# midimixer-st-eval.net
KiCad netlist of a schematic drawn in EAGLE
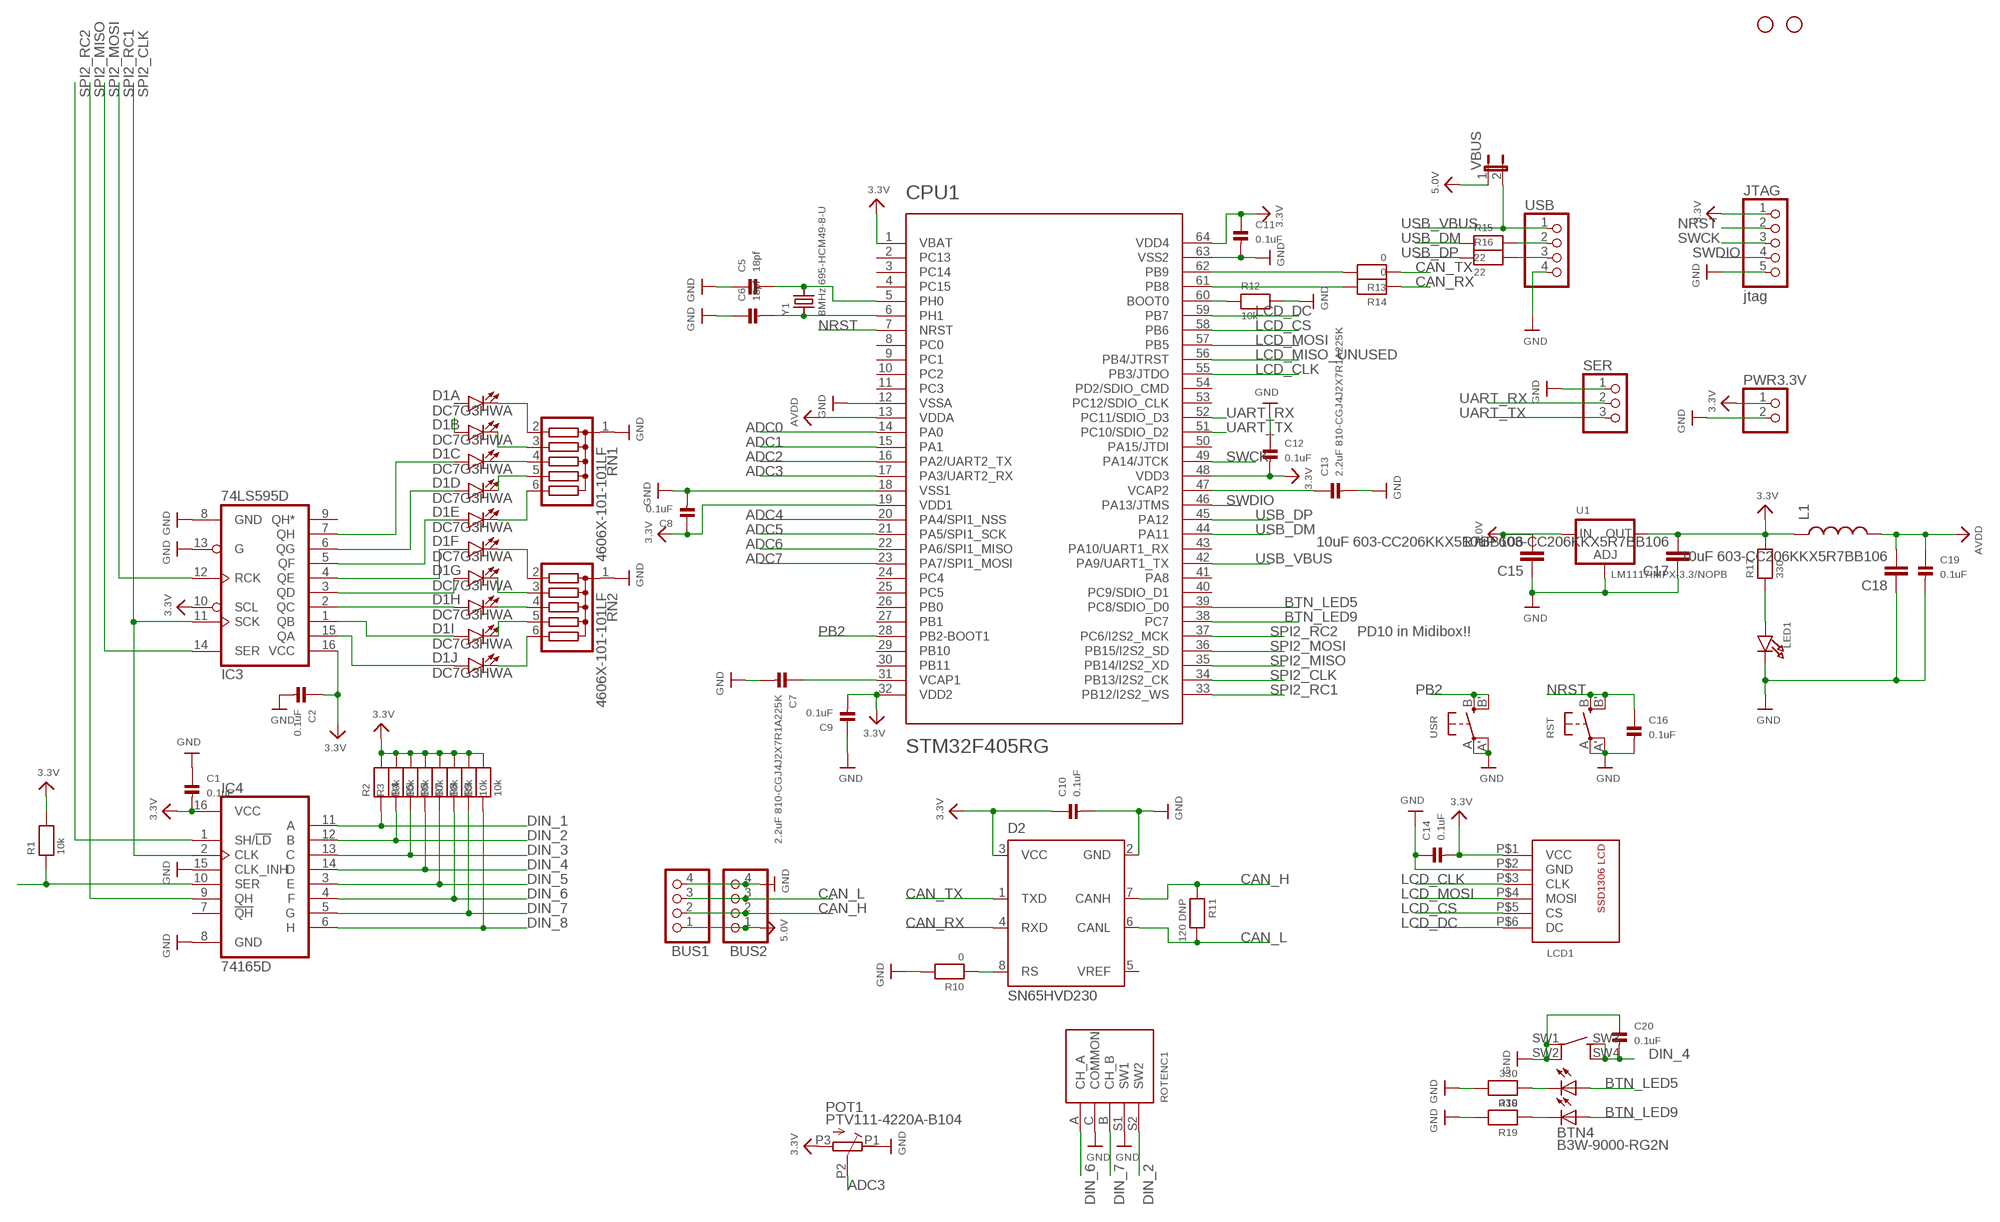
[diagram p0: schematic, sheet 1]

(export (version "E")
  (design (tool "Eeschema 10.0.6"))
  (components
    (comp (ref "BTN4")
      (value "B3W-9000-RG2N")
      (footprint "eagle-import:B3W-9000-X2X")
      (libsource (lib "eagle-import") (part "B3W-9000-RG2N"))
    )
    (comp (ref "BUS1")
      (value "HEADER-1X4ROUND")
      (footprint "eagle-import:1X04_ROUND")
      (libsource (lib "eagle-import") (part "HEADER-1X4ROUND"))
    )
    (comp (ref "BUS2")
      (value "HEADER-1X4ROUND")
      (footprint "eagle-import:1X04_ROUND")
      (libsource (lib "eagle-import") (part "HEADER-1X4ROUND"))
    )
    (comp (ref "C1")
      (value "0.1uF")
      (footprint "eagle-import:0603")
      (libsource (lib "eagle-import") (part "CAP_CERAMIC0603"))
    )
    (comp (ref "C2")
      (value "0.1uF")
      (footprint "eagle-import:0603")
      (libsource (lib "eagle-import") (part "CAP_CERAMIC0603"))
    )
    (comp (ref "C5")
      (value "18pf")
      (footprint "eagle-import:0603")
      (libsource (lib "eagle-import") (part "CAP_CERAMIC0603"))
    )
    (comp (ref "C6")
      (value "18pf")
      (footprint "eagle-import:0603")
      (libsource (lib "eagle-import") (part "CAP_CERAMIC0603"))
    )
    (comp (ref "C7")
      (value "2.2uF 810-CGJ4J2X7R1A225K")
      (footprint "eagle-import:0805")
      (libsource (lib "eagle-import") (part "CAP_CERAMIC0805"))
    )
    (comp (ref "C8")
      (value "0.1uF")
      (footprint "eagle-import:0603")
      (libsource (lib "eagle-import") (part "CAP_CERAMIC0603"))
    )
    (comp (ref "C9")
      (value "0.1uF")
      (footprint "eagle-import:0603")
      (libsource (lib "eagle-import") (part "CAP_CERAMIC0603"))
    )
    (comp (ref "C10")
      (value "0.1uF")
      (footprint "eagle-import:0603")
      (libsource (lib "eagle-import") (part "CAP_CERAMIC0603"))
    )
    (comp (ref "C11")
      (value "0.1uF")
      (footprint "eagle-import:0603")
      (libsource (lib "eagle-import") (part "CAP_CERAMIC0603"))
    )
    (comp (ref "C12")
      (value "0.1uF")
      (footprint "eagle-import:0603")
      (libsource (lib "eagle-import") (part "CAP_CERAMIC0603"))
    )
    (comp (ref "C13")
      (value "2.2uF 810-CGJ4J2X7R1A225K")
      (footprint "eagle-import:0805")
      (libsource (lib "eagle-import") (part "CAP_CERAMIC0805"))
    )
    (comp (ref "C14")
      (value "0.1uF")
      (footprint "eagle-import:0603")
      (libsource (lib "eagle-import") (part "CAP_CERAMIC0603"))
    )
    (comp (ref "C15")
      (value "10uF 603-CC206KKX5R7BB106")
      (footprint "eagle-import:1206")
      (libsource (lib "eagle-import") (part "CAP1206"))
    )
    (comp (ref "C16")
      (value "0.1uF")
      (footprint "eagle-import:0603")
      (libsource (lib "eagle-import") (part "CAP_CERAMIC0603"))
    )
    (comp (ref "C17")
      (value "10uF 603-CC206KKX5R7BB106")
      (footprint "eagle-import:1206")
      (libsource (lib "eagle-import") (part "CAP1206"))
    )
    (comp (ref "C18")
      (value "10uF 603-CC206KKX5R7BB106")
      (footprint "eagle-import:1206")
      (libsource (lib "eagle-import") (part "CAP1206"))
    )
    (comp (ref "C19")
      (value "0.1uF")
      (footprint "eagle-import:0603")
      (libsource (lib "eagle-import") (part "CAP_CERAMIC0603"))
    )
    (comp (ref "C20")
      (value "0.1uF")
      (footprint "eagle-import:0603")
      (libsource (lib "eagle-import") (part "CAP_CERAMIC0603"))
    )
    (comp (ref "CPU1")
      (value "STM32F405RG")
      (footprint "eagle-import:TQFP64")
      (libsource (lib "eagle-import") (part "STM32F405RG"))
    )
    (comp (ref "D1")
      (value "DC7G3HWA")
      (footprint "eagle-import:LED_BARGAPH_10")
      (libsource (lib "eagle-import") (part "LED_BARGRAPH_10"))
    )
    (comp (ref "D2")
      (value "SN65HVD230")
      (footprint "eagle-import:SO8")
      (libsource (lib "eagle-import") (part "SN65HVD230"))
    )
    (comp (ref "H1")
      (value "STAND-OFF")
      (footprint "eagle-import:STAND-OFF")
      (libsource (lib "eagle-import") (part "STAND-OFF"))
    )
    (comp (ref "H3")
      (value "STAND-OFF")
      (footprint "eagle-import:STAND-OFF")
      (libsource (lib "eagle-import") (part "STAND-OFF"))
    )
    (comp (ref "IC3")
      (value "74LS595D")
      (footprint "eagle-import:SO16")
      (libsource (lib "eagle-import") (part "74595DLS"))
    )
    (comp (ref "IC4")
      (value "74165D")
      (footprint "eagle-import:SO16")
      (libsource (lib "eagle-import") (part "74165D"))
    )
    (comp (ref "JTAG")
      (value "jtag")
      (footprint "eagle-import:1X05_ROUND_76")
      (libsource (lib "eagle-import") (part "HEADER-1X576MIL"))
    )
    (comp (ref "L1")
      (value "INDUCTOR0805")
      (footprint "eagle-import:0805")
      (libsource (lib "eagle-import") (part "INDUCTOR0805"))
    )
    (comp (ref "LCD1")
      (value "SSD1306-ALI")
      (footprint "eagle-import:SSD1306-ALI")
      (libsource (lib "eagle-import") (part "SSD1306-ALI"))
    )
    (comp (ref "LED1")
      (value "LED0603")
      (footprint "eagle-import:CHIPLED_0603")
      (libsource (lib "eagle-import") (part "LED0603"))
    )
    (comp (ref "POT1")
      (value "PTV111-4220A-B104")
      (footprint "eagle-import:PTV111-4")
      (libsource (lib "eagle-import") (part "PTV111-4220A-B104"))
    )
    (comp (ref "PWR3.3V")
      (value "HEADER-1X2ROUND")
      (footprint "eagle-import:1X02_ROUND")
      (libsource (lib "eagle-import") (part "HEADER-1X2ROUND"))
    )
    (comp (ref "R1")
      (value "10k")
      (footprint "eagle-import:_0603")
      (libsource (lib "eagle-import") (part "RESISTOR_0603"))
    )
    (comp (ref "R2")
      (value "10k")
      (footprint "eagle-import:_0603")
      (libsource (lib "eagle-import") (part "RESISTOR_0603"))
    )
    (comp (ref "R3")
      (value "10k")
      (footprint "eagle-import:_0603")
      (libsource (lib "eagle-import") (part "RESISTOR_0603"))
    )
    (comp (ref "R4")
      (value "10k")
      (footprint "eagle-import:_0603")
      (libsource (lib "eagle-import") (part "RESISTOR_0603"))
    )
    (comp (ref "R5")
      (value "10k")
      (footprint "eagle-import:_0603")
      (libsource (lib "eagle-import") (part "RESISTOR_0603"))
    )
    (comp (ref "R6")
      (value "10k")
      (footprint "eagle-import:_0603")
      (libsource (lib "eagle-import") (part "RESISTOR_0603"))
    )
    (comp (ref "R7")
      (value "10k")
      (footprint "eagle-import:_0603")
      (libsource (lib "eagle-import") (part "RESISTOR_0603"))
    )
    (comp (ref "R8")
      (value "10k")
      (footprint "eagle-import:_0603")
      (libsource (lib "eagle-import") (part "RESISTOR_0603"))
    )
    (comp (ref "R9")
      (value "10k")
      (footprint "eagle-import:_0603")
      (libsource (lib "eagle-import") (part "RESISTOR_0603"))
    )
    (comp (ref "R10")
      (value "0")
      (footprint "eagle-import:_0603")
      (libsource (lib "eagle-import") (part "RESISTOR_0603"))
    )
    (comp (ref "R11")
      (value "120 DNP")
      (footprint "eagle-import:_0603")
      (libsource (lib "eagle-import") (part "RESISTOR_0603"))
    )
    (comp (ref "R12")
      (value "10k")
      (footprint "eagle-import:_0603")
      (libsource (lib "eagle-import") (part "RESISTOR_0603"))
    )
    (comp (ref "R13")
      (value "0")
      (footprint "eagle-import:_0603")
      (libsource (lib "eagle-import") (part "RESISTOR_0603"))
    )
    (comp (ref "R14")
      (value "0")
      (footprint "eagle-import:_0603")
      (libsource (lib "eagle-import") (part "RESISTOR_0603"))
    )
    (comp (ref "R15")
      (value "22")
      (footprint "eagle-import:0603")
      (libsource (lib "eagle-import") (part "RESISTOR0603"))
    )
    (comp (ref "R16")
      (value "22")
      (footprint "eagle-import:0603")
      (libsource (lib "eagle-import") (part "RESISTOR0603"))
    )
    (comp (ref "R17")
      (value "330")
      (footprint "eagle-import:0603")
      (libsource (lib "eagle-import") (part "RESISTOR0603"))
    )
    (comp (ref "R18")
      (value "330")
      (footprint "eagle-import:0603")
      (libsource (lib "eagle-import") (part "RESISTOR0603"))
    )
    (comp (ref "R19")
      (value "330")
      (footprint "eagle-import:0603")
      (libsource (lib "eagle-import") (part "RESISTOR0603"))
    )
    (comp (ref "RN1")
      (value "4606X-101-101LF")
      (footprint "eagle-import:SIL6")
      (libsource (lib "eagle-import") (part "G05R"))
    )
    (comp (ref "RN2")
      (value "4606X-101-101LF")
      (footprint "eagle-import:SIL6")
      (libsource (lib "eagle-import") (part "G05R"))
    )
    (comp (ref "ROTENC1")
      (value "PEC11-4215K-S0024")
      (footprint "eagle-import:PEC111-4XXXK-SXXXX")
      (libsource (lib "eagle-import") (part "PEC11-4215K-S0024"))
    )
    (comp (ref "RST")
      (value "SWITCH_TACT_SMT")
      (footprint "eagle-import:EVQ-Q2")
      (libsource (lib "eagle-import") (part "SWITCH_TACT_SMT"))
    )
    (comp (ref "SER")
      (value "HEADER-1X3ROUND")
      (footprint "eagle-import:1X03_ROUND")
      (libsource (lib "eagle-import") (part "HEADER-1X3ROUND"))
    )
    (comp (ref "U1")
      (value "LM1117IMPX-3.3/NOPB")
      (footprint "eagle-import:SOT223-R")
      (libsource (lib "eagle-import") (part "LM1117SOT223-REFLOW"))
    )
    (comp (ref "USB")
      (value "HEADER-1X4ROUND")
      (footprint "eagle-import:1X04_ROUND")
      (libsource (lib "eagle-import") (part "HEADER-1X4ROUND"))
    )
    (comp (ref "USR")
      (value "SWITCH_TACT_SMT")
      (footprint "eagle-import:EVQ-Q2")
      (libsource (lib "eagle-import") (part "SWITCH_TACT_SMT"))
    )
    (comp (ref "VBUS")
      (value "JUMPER2")
      (footprint "eagle-import:JUMPER2")
      (libsource (lib "eagle-import") (part "JUMPER2"))
    )
    (comp (ref "Y1")
      (value "8MHz 695-HCM49-8-U")
      (footprint "eagle-import:HC49UP")
      (libsource (lib "eagle-import") (part "CRYSTALSMD"))
    )
  )
  (nets
    (net (code "1") (name "/ADC0") (class "Default")
      (node (ref "CPU1") (pin "14") (pinfunction "PA0_14") (pintype "bidirectional"))
    )
    (net (code "2") (name "/ADC1") (class "Default")
      (node (ref "CPU1") (pin "15") (pinfunction "PA1_15") (pintype "bidirectional"))
    )
    (net (code "3") (name "/ADC2") (class "Default")
      (node (ref "CPU1") (pin "16") (pinfunction "PA2/UART2_TX_16") (pintype "bidirectional"))
    )
    (net (code "4") (name "/ADC3") (class "Default")
      (node (ref "CPU1") (pin "17") (pinfunction "PA3/UART2_RX_17") (pintype "bidirectional"))
      (node (ref "POT1") (pin "P2") (pinfunction "S_P2") (pintype "passive"))
    )
    (net (code "5") (name "/ADC4") (class "Default")
      (node (ref "CPU1") (pin "20") (pinfunction "PA4/SPI1_NSS_20") (pintype "bidirectional"))
    )
    (net (code "6") (name "/ADC5") (class "Default")
      (node (ref "CPU1") (pin "21") (pinfunction "PA5/SPI1_SCK_21") (pintype "bidirectional"))
    )
    (net (code "7") (name "/ADC6") (class "Default")
      (node (ref "CPU1") (pin "22") (pinfunction "PA6/SPI1_MISO_22") (pintype "bidirectional"))
    )
    (net (code "8") (name "/ADC7") (class "Default")
      (node (ref "CPU1") (pin "23") (pinfunction "PA7/SPI1_MOSI_23") (pintype "bidirectional"))
    )
    (net (code "9") (name "/BTN_LED5") (class "Default")
      (node (ref "BTN4") (pin "LED1+") (pinfunction "LED1+_LED1+") (pintype "passive"))
      (node (ref "CPU1") (pin "39") (pinfunction "PC8/SDIO_D0_39") (pintype "bidirectional"))
    )
    (net (code "10") (name "/BTN_LED9") (class "Default")
      (node (ref "BTN4") (pin "LED2+") (pinfunction "LED2+_LED2+") (pintype "passive"))
      (node (ref "CPU1") (pin "38") (pinfunction "PC7_38") (pintype "bidirectional"))
    )
    (net (code "11") (name "/CAN_H") (class "Default")
      (node (ref "BUS1") (pin "2") (pinfunction "2_2") (pintype "passive"))
      (node (ref "BUS2") (pin "2") (pinfunction "2_2") (pintype "passive"))
      (node (ref "D2") (pin "7") (pinfunction "CANH_7") (pintype "bidirectional"))
      (node (ref "R11") (pin "1") (pinfunction "1_1") (pintype "passive"))
    )
    (net (code "12") (name "/CAN_L") (class "Default")
      (node (ref "BUS1") (pin "3") (pinfunction "3_3") (pintype "passive"))
      (node (ref "BUS2") (pin "3") (pinfunction "3_3") (pintype "passive"))
      (node (ref "D2") (pin "6") (pinfunction "CANL_6") (pintype "bidirectional"))
      (node (ref "R11") (pin "2") (pinfunction "2_2") (pintype "passive"))
    )
    (net (code "13") (name "/CAN_RX") (class "Default")
      (node (ref "D2") (pin "4") (pinfunction "RXD_4") (pintype "output"))
      (node (ref "R14") (pin "1") (pinfunction "1_1") (pintype "passive"))
    )
    (net (code "14") (name "/CAN_TX") (class "Default")
      (node (ref "D2") (pin "1") (pinfunction "TXD_1") (pintype "input"))
      (node (ref "R13") (pin "1") (pinfunction "1_1") (pintype "passive"))
    )
    (net (code "15") (name "/DIN_1") (class "Default")
      (node (ref "IC4") (pin "11") (pinfunction "A_11") (pintype "tri_state"))
      (node (ref "R2") (pin "1") (pinfunction "1_1") (pintype "passive"))
    )
    (net (code "16") (name "/DIN_2") (class "Default")
      (node (ref "IC4") (pin "12") (pinfunction "B_12") (pintype "tri_state"))
      (node (ref "R3") (pin "1") (pinfunction "1_1") (pintype "passive"))
      (node (ref "ROTENC1") (pin "S2") (pinfunction "SW2_S2") (pintype "bidirectional"))
    )
    (net (code "17") (name "/DIN_3") (class "Default")
      (node (ref "IC4") (pin "13") (pinfunction "C_13") (pintype "tri_state"))
      (node (ref "R4") (pin "1") (pinfunction "1_1") (pintype "passive"))
    )
    (net (code "18") (name "/DIN_4") (class "Default")
      (node (ref "BTN4") (pin "SW3") (pinfunction "SW2_A_SW3") (pintype "passive"))
      (node (ref "BTN4") (pin "SW4") (pinfunction "SW2_B_SW4") (pintype "passive"))
      (node (ref "C20") (pin "2") (pinfunction "P$2_2") (pintype "passive"))
      (node (ref "IC4") (pin "14") (pinfunction "D_14") (pintype "tri_state"))
      (node (ref "R5") (pin "1") (pinfunction "1_1") (pintype "passive"))
    )
    (net (code "19") (name "/DIN_5") (class "Default")
      (node (ref "IC4") (pin "3") (pinfunction "E_3") (pintype "tri_state"))
      (node (ref "R6") (pin "1") (pinfunction "1_1") (pintype "passive"))
    )
    (net (code "20") (name "/DIN_6") (class "Default")
      (node (ref "IC4") (pin "4") (pinfunction "F_4") (pintype "tri_state"))
      (node (ref "R7") (pin "1") (pinfunction "1_1") (pintype "passive"))
      (node (ref "ROTENC1") (pin "A") (pinfunction "CH_A_A") (pintype "output"))
    )
    (net (code "21") (name "/DIN_7") (class "Default")
      (node (ref "IC4") (pin "5") (pinfunction "G_5") (pintype "tri_state"))
      (node (ref "R8") (pin "1") (pinfunction "1_1") (pintype "passive"))
      (node (ref "ROTENC1") (pin "B") (pinfunction "CH_B_B") (pintype "output"))
    )
    (net (code "22") (name "/DIN_8") (class "Default")
      (node (ref "IC4") (pin "6") (pinfunction "H_6") (pintype "tri_state"))
      (node (ref "R9") (pin "1") (pinfunction "1_1") (pintype "passive"))
    )
    (net (code "23") (name "/LCD_CLK") (class "Default")
      (node (ref "CPU1") (pin "55") (pinfunction "PB3/JTDO_55") (pintype "bidirectional"))
      (node (ref "LCD1") (pin "P$3") (pinfunction "CLK_P$3") (pintype "bidirectional"))
    )
    (net (code "24") (name "/LCD_CS") (class "Default")
      (node (ref "CPU1") (pin "58") (pinfunction "PB6_58") (pintype "bidirectional"))
      (node (ref "LCD1") (pin "P$5") (pinfunction "CS_P$5") (pintype "bidirectional"))
    )
    (net (code "25") (name "/LCD_DC") (class "Default")
      (node (ref "CPU1") (pin "59") (pinfunction "PB7_59") (pintype "bidirectional"))
      (node (ref "LCD1") (pin "P$6") (pinfunction "DC_P$6") (pintype "bidirectional"))
    )
    (net (code "26") (name "/LCD_MISO_UNUSED") (class "Default")
      (node (ref "CPU1") (pin "56") (pinfunction "PB4/JTRST_56") (pintype "bidirectional"))
    )
    (net (code "27") (name "/LCD_MOSI") (class "Default")
      (node (ref "CPU1") (pin "57") (pinfunction "PB5_57") (pintype "bidirectional"))
      (node (ref "LCD1") (pin "P$4") (pinfunction "MOSI_P$4") (pintype "bidirectional"))
    )
    (net (code "28") (name "/NRST") (class "Default")
      (node (ref "C16") (pin "1") (pinfunction "P$1_1") (pintype "passive"))
      (node (ref "CPU1") (pin "7") (pinfunction "NRST_7") (pintype "bidirectional"))
      (node (ref "JTAG") (pin "2") (pinfunction "2_2") (pintype "passive"))
      (node (ref "RST") (pin "B") (pinfunction "S_B") (pintype "passive"))
      (node (ref "RST") (pin "B'") (pinfunction "S1_B'") (pintype "passive"))
    )
    (net (code "29") (name "/PB2") (class "Default")
      (node (ref "CPU1") (pin "28") (pinfunction "PB2-BOOT1_28") (pintype "bidirectional"))
      (node (ref "USR") (pin "B") (pinfunction "S_B") (pintype "passive"))
      (node (ref "USR") (pin "B'") (pinfunction "S1_B'") (pintype "passive"))
    )
    (net (code "30") (name "/SPI2_CLK") (class "Default")
      (node (ref "CPU1") (pin "34") (pinfunction "PB13/I2S2_CK_34") (pintype "bidirectional"))
      (node (ref "IC3") (pin "11") (pinfunction "SCK_11") (pintype "input"))
      (node (ref "IC4") (pin "2") (pinfunction "CLK_2") (pintype "input"))
    )
    (net (code "31") (name "/SPI2_MISO") (class "Default")
      (node (ref "CPU1") (pin "35") (pinfunction "PB14/I2S2_XD_35") (pintype "bidirectional"))
      (node (ref "IC4") (pin "9") (pinfunction "QH_9") (pintype "tri_state"))
    )
    (net (code "32") (name "/SPI2_MOSI") (class "Default")
      (node (ref "CPU1") (pin "36") (pinfunction "PB15/I2S2_SD_36") (pintype "bidirectional"))
      (node (ref "IC3") (pin "14") (pinfunction "SER_14") (pintype "input"))
    )
    (net (code "33") (name "/SPI2_RC1") (class "Default")
      (node (ref "CPU1") (pin "33") (pinfunction "PB12/I2S2_WS_33") (pintype "bidirectional"))
      (node (ref "IC3") (pin "12") (pinfunction "RCK_12") (pintype "input"))
    )
    (net (code "34") (name "/SPI2_RC2") (class "Default")
      (node (ref "CPU1") (pin "37") (pinfunction "PC6/I2S2_MCK_37") (pintype "bidirectional"))
      (node (ref "IC4") (pin "1") (pinfunction "SH/~{LD}_1") (pintype "input"))
    )
    (net (code "35") (name "/SWCK") (class "Default")
      (node (ref "CPU1") (pin "49") (pinfunction "PA14/JTCK_49") (pintype "bidirectional"))
      (node (ref "JTAG") (pin "3") (pinfunction "3_3") (pintype "passive"))
    )
    (net (code "36") (name "/SWDIO") (class "Default")
      (node (ref "CPU1") (pin "46") (pinfunction "PA13/JTMS_46") (pintype "bidirectional"))
      (node (ref "JTAG") (pin "4") (pinfunction "4_4") (pintype "passive"))
    )
    (net (code "37") (name "/UART_RX") (class "Default")
      (node (ref "CPU1") (pin "52") (pinfunction "PC11/SDIO_D3_52") (pintype "bidirectional"))
      (node (ref "SER") (pin "2") (pinfunction "2_2") (pintype "passive"))
    )
    (net (code "38") (name "/UART_TX") (class "Default")
      (node (ref "CPU1") (pin "51") (pinfunction "PC10/SDIO_D2_51") (pintype "bidirectional"))
      (node (ref "SER") (pin "3") (pinfunction "3_3") (pintype "passive"))
    )
    (net (code "39") (name "/USB_DM") (class "Default")
      (node (ref "CPU1") (pin "44") (pinfunction "PA11_44") (pintype "bidirectional"))
      (node (ref "R15") (pin "1") (pinfunction "1_1") (pintype "passive"))
    )
    (net (code "40") (name "/USB_DP") (class "Default")
      (node (ref "CPU1") (pin "45") (pinfunction "PA12_45") (pintype "bidirectional"))
      (node (ref "R16") (pin "1") (pinfunction "1_1") (pintype "passive"))
    )
    (net (code "41") (name "/USB_VBUS") (class "Default")
      (node (ref "CPU1") (pin "42") (pinfunction "PA9/UART1_TX_42") (pintype "bidirectional"))
      (node (ref "USB") (pin "1") (pinfunction "1_1") (pintype "passive"))
      (node (ref "VBUS") (pin "2") (pinfunction "2_2") (pintype "passive"))
    )
    (net (code "42") (name "3.3V") (class "Default")
      (node (ref "C1") (pin "2") (pinfunction "P$2_2") (pintype "passive"))
      (node (ref "C10") (pin "1") (pinfunction "P$1_1") (pintype "passive"))
      (node (ref "C11") (pin "1") (pinfunction "P$1_1") (pintype "passive"))
      (node (ref "C12") (pin "2") (pinfunction "P$2_2") (pintype "passive"))
      (node (ref "C14") (pin "2") (pinfunction "P$2_2") (pintype "passive"))
      (node (ref "C17") (pin "2") (pinfunction "2_2") (pintype "passive"))
      (node (ref "C2") (pin "1") (pinfunction "P$1_1") (pintype "passive"))
      (node (ref "C8") (pin "1") (pinfunction "P$1_1") (pintype "passive"))
      (node (ref "C9") (pin "2") (pinfunction "P$2_2") (pintype "passive"))
      (node (ref "CPU1") (pin "1") (pinfunction "VBAT_1") (pintype "bidirectional"))
      (node (ref "CPU1") (pin "19") (pinfunction "VDD1_19") (pintype "bidirectional"))
      (node (ref "CPU1") (pin "32") (pinfunction "VDD2_32") (pintype "bidirectional"))
      (node (ref "CPU1") (pin "48") (pinfunction "VDD3_48") (pintype "bidirectional"))
      (node (ref "CPU1") (pin "64") (pinfunction "VDD4_64") (pintype "bidirectional"))
      (node (ref "D2") (pin "3") (pinfunction "VCC_3") (pintype "power_in"))
      (node (ref "IC3") (pin "10") (pinfunction "SCL_10") (pintype "input"))
      (node (ref "IC3") (pin "16") (pinfunction "VCC_16") (pintype "power_in"))
      (node (ref "IC4") (pin "16") (pinfunction "VCC_16") (pintype "power_in"))
      (node (ref "JTAG") (pin "1") (pinfunction "1_1") (pintype "passive"))
      (node (ref "L1") (pin "1") (pinfunction "1_1") (pintype "passive"))
      (node (ref "LCD1") (pin "P$1") (pinfunction "VCC_P$1") (pintype "bidirectional"))
      (node (ref "POT1") (pin "P3") (pinfunction "E_P3") (pintype "passive"))
      (node (ref "PWR3.3V") (pin "1") (pinfunction "1_1") (pintype "passive"))
      (node (ref "R1") (pin "2") (pinfunction "2_2") (pintype "passive"))
      (node (ref "R17") (pin "2") (pinfunction "2_2") (pintype "passive"))
      (node (ref "R2") (pin "2") (pinfunction "2_2") (pintype "passive"))
      (node (ref "R3") (pin "2") (pinfunction "2_2") (pintype "passive"))
      (node (ref "R4") (pin "2") (pinfunction "2_2") (pintype "passive"))
      (node (ref "R5") (pin "2") (pinfunction "2_2") (pintype "passive"))
      (node (ref "R6") (pin "2") (pinfunction "2_2") (pintype "passive"))
      (node (ref "R7") (pin "2") (pinfunction "2_2") (pintype "passive"))
      (node (ref "R8") (pin "2") (pinfunction "2_2") (pintype "passive"))
      (node (ref "R9") (pin "2") (pinfunction "2_2") (pintype "passive"))
      (node (ref "U1") (pin "2") (pinfunction "OUT_2") (pintype "passive"))
    )
    (net (code "43") (name "5.0V") (class "Default")
      (node (ref "BUS1") (pin "1") (pinfunction "1_1") (pintype "passive"))
      (node (ref "BUS2") (pin "1") (pinfunction "1_1") (pintype "passive"))
      (node (ref "C15") (pin "2") (pinfunction "2_2") (pintype "passive"))
      (node (ref "U1") (pin "3") (pinfunction "IN_3") (pintype "input"))
      (node (ref "VBUS") (pin "1") (pinfunction "1_1") (pintype "passive"))
    )
    (net (code "44") (name "AVDD") (class "Default")
      (node (ref "C18") (pin "2") (pinfunction "2_2") (pintype "passive"))
      (node (ref "C19") (pin "1") (pinfunction "P$1_1") (pintype "passive"))
      (node (ref "CPU1") (pin "13") (pinfunction "VDDA_13") (pintype "bidirectional"))
      (node (ref "L1") (pin "2") (pinfunction "2_2") (pintype "passive"))
    )
    (net (code "45") (name "GND") (class "Default")
      (node (ref "BTN4") (pin "SW1") (pinfunction "SW1_A_SW1") (pintype "passive"))
      (node (ref "BTN4") (pin "SW2") (pinfunction "SW1_B_SW2") (pintype "passive"))
      (node (ref "BUS1") (pin "4") (pinfunction "4_4") (pintype "passive"))
      (node (ref "BUS2") (pin "4") (pinfunction "4_4") (pintype "passive"))
      (node (ref "C1") (pin "1") (pinfunction "P$1_1") (pintype "passive"))
      (node (ref "C10") (pin "2") (pinfunction "P$2_2") (pintype "passive"))
      (node (ref "C11") (pin "2") (pinfunction "P$2_2") (pintype "passive"))
      (node (ref "C12") (pin "1") (pinfunction "P$1_1") (pintype "passive"))
      (node (ref "C13") (pin "2") (pinfunction "P$2_2") (pintype "passive"))
      (node (ref "C14") (pin "1") (pinfunction "P$1_1") (pintype "passive"))
      (node (ref "C15") (pin "1") (pinfunction "1_1") (pintype "passive"))
      (node (ref "C16") (pin "2") (pinfunction "P$2_2") (pintype "passive"))
      (node (ref "C17") (pin "1") (pinfunction "1_1") (pintype "passive"))
      (node (ref "C18") (pin "1") (pinfunction "1_1") (pintype "passive"))
      (node (ref "C19") (pin "2") (pinfunction "P$2_2") (pintype "passive"))
      (node (ref "C2") (pin "2") (pinfunction "P$2_2") (pintype "passive"))
      (node (ref "C20") (pin "1") (pinfunction "P$1_1") (pintype "passive"))
      (node (ref "C5") (pin "1") (pinfunction "P$1_1") (pintype "passive"))
      (node (ref "C6") (pin "1") (pinfunction "P$1_1") (pintype "passive"))
      (node (ref "C7") (pin "2") (pinfunction "P$2_2") (pintype "passive"))
      (node (ref "C8") (pin "2") (pinfunction "P$2_2") (pintype "passive"))
      (node (ref "C9") (pin "1") (pinfunction "P$1_1") (pintype "passive"))
      (node (ref "CPU1") (pin "12") (pinfunction "VSSA_12") (pintype "bidirectional"))
      (node (ref "CPU1") (pin "18") (pinfunction "VSS1_18") (pintype "bidirectional"))
      (node (ref "CPU1") (pin "63") (pinfunction "VSS2_63") (pintype "bidirectional"))
      (node (ref "D2") (pin "2") (pinfunction "GND_2") (pintype "power_in"))
      (node (ref "IC3") (pin "13") (pinfunction "G_13") (pintype "input"))
      (node (ref "IC3") (pin "8") (pinfunction "GND_8") (pintype "power_in"))
      (node (ref "IC4") (pin "15") (pinfunction "CLK_INH_15") (pintype "input"))
      (node (ref "IC4") (pin "8") (pinfunction "GND_8") (pintype "power_in"))
      (node (ref "JTAG") (pin "5") (pinfunction "5_5") (pintype "passive"))
      (node (ref "LCD1") (pin "P$2") (pinfunction "GND_P$2") (pintype "bidirectional"))
      (node (ref "LED1") (pin "C") (pinfunction "C_C") (pintype "passive"))
      (node (ref "POT1") (pin "P1") (pinfunction "A_P1") (pintype "passive"))
      (node (ref "PWR3.3V") (pin "2") (pinfunction "2_2") (pintype "passive"))
      (node (ref "R10") (pin "2") (pinfunction "2_2") (pintype "passive"))
      (node (ref "R12") (pin "2") (pinfunction "2_2") (pintype "passive"))
      (node (ref "R18") (pin "2") (pinfunction "2_2") (pintype "passive"))
      (node (ref "R19") (pin "2") (pinfunction "2_2") (pintype "passive"))
      (node (ref "RN1") (pin "1") (pinfunction "1_1") (pintype "passive"))
      (node (ref "RN2") (pin "1") (pinfunction "1_1") (pintype "passive"))
      (node (ref "ROTENC1") (pin "C") (pinfunction "COMMON_C") (pintype "input"))
      (node (ref "ROTENC1") (pin "S1") (pinfunction "SW1_S1") (pintype "bidirectional"))
      (node (ref "RST") (pin "A") (pinfunction "P_A") (pintype "passive"))
      (node (ref "RST") (pin "A'") (pinfunction "P1_A'") (pintype "passive"))
      (node (ref "SER") (pin "1") (pinfunction "1_1") (pintype "passive"))
      (node (ref "U1") (pin "1") (pinfunction "ADJ_1") (pintype "input"))
      (node (ref "USB") (pin "4") (pinfunction "4_4") (pintype "passive"))
      (node (ref "USR") (pin "A") (pinfunction "P_A") (pintype "passive"))
      (node (ref "USR") (pin "A'") (pinfunction "P1_A'") (pintype "passive"))
    )
    (net (code "46") (name "Net-(BTN4-PadLED1-)") (class "Default")
      (node (ref "BTN4") (pin "LED1-") (pinfunction "LED1-_LED1-") (pintype "passive"))
      (node (ref "R18") (pin "1") (pinfunction "1_1") (pintype "passive"))
    )
    (net (code "47") (name "Net-(BTN4-PadLED2-)") (class "Default")
      (node (ref "BTN4") (pin "LED2-") (pinfunction "LED2-_LED2-") (pintype "passive"))
      (node (ref "R19") (pin "1") (pinfunction "1_1") (pintype "passive"))
    )
    (net (code "48") (name "Net-(C5-P$2)") (class "Default")
      (node (ref "C5") (pin "2") (pinfunction "P$2_2") (pintype "passive"))
      (node (ref "CPU1") (pin "5") (pinfunction "PH0_5") (pintype "bidirectional"))
      (node (ref "Y1") (pin "2") (pinfunction "2_2") (pintype "passive"))
    )
    (net (code "49") (name "Net-(C6-P$2)") (class "Default")
      (node (ref "C6") (pin "2") (pinfunction "P$2_2") (pintype "passive"))
      (node (ref "CPU1") (pin "6") (pinfunction "PH1_6") (pintype "bidirectional"))
      (node (ref "Y1") (pin "1") (pinfunction "1_1") (pintype "passive"))
    )
    (net (code "50") (name "Net-(C7-P$1)") (class "Default")
      (node (ref "C7") (pin "1") (pinfunction "P$1_1") (pintype "passive"))
      (node (ref "CPU1") (pin "31") (pinfunction "VCAP1_31") (pintype "bidirectional"))
    )
    (net (code "51") (name "Net-(C13-P$1)") (class "Default")
      (node (ref "C13") (pin "1") (pinfunction "P$1_1") (pintype "passive"))
      (node (ref "CPU1") (pin "47") (pinfunction "VCAP2_47") (pintype "bidirectional"))
    )
    (net (code "52") (name "Net-(CPU1-BOOT0)") (class "Default")
      (node (ref "CPU1") (pin "60") (pinfunction "BOOT0_60") (pintype "bidirectional"))
      (node (ref "R12") (pin "1") (pinfunction "1_1") (pintype "passive"))
    )
    (net (code "53") (name "Net-(CPU1-PB8)") (class "Default")
      (node (ref "CPU1") (pin "61") (pinfunction "PB8_61") (pintype "bidirectional"))
      (node (ref "R14") (pin "2") (pinfunction "2_2") (pintype "passive"))
    )
    (net (code "54") (name "Net-(CPU1-PB9)") (class "Default")
      (node (ref "CPU1") (pin "62") (pinfunction "PB9_62") (pintype "bidirectional"))
      (node (ref "R13") (pin "2") (pinfunction "2_2") (pintype "passive"))
    )
    (net (code "55") (name "Net-(D1A-C)") (class "Default")
      (node (ref "D1") (pin "20") (pinfunction "C_20") (pintype "passive"))
      (node (ref "RN1") (pin "2") (pinfunction "2_2") (pintype "passive"))
    )
    (net (code "56") (name "Net-(D1B-C)") (class "Default")
      (node (ref "D1") (pin "19") (pinfunction "C_19") (pintype "passive"))
      (node (ref "RN1") (pin "3") (pinfunction "3_3") (pintype "passive"))
    )
    (net (code "57") (name "Net-(D1C-A)") (class "Default")
      (node (ref "D1") (pin "3") (pinfunction "A_3") (pintype "passive"))
      (node (ref "IC3") (pin "7") (pinfunction "QH_7") (pintype "tri_state"))
    )
    (net (code "58") (name "Net-(D1C-C)") (class "Default")
      (node (ref "D1") (pin "18") (pinfunction "C_18") (pintype "passive"))
      (node (ref "RN1") (pin "4") (pinfunction "4_4") (pintype "passive"))
    )
    (net (code "59") (name "Net-(D1D-A)") (class "Default")
      (node (ref "D1") (pin "4") (pinfunction "A_4") (pintype "passive"))
      (node (ref "IC3") (pin "6") (pinfunction "QG_6") (pintype "tri_state"))
    )
    (net (code "60") (name "Net-(D1D-C)") (class "Default")
      (node (ref "D1") (pin "17") (pinfunction "C_17") (pintype "passive"))
      (node (ref "RN1") (pin "5") (pinfunction "5_5") (pintype "passive"))
    )
    (net (code "61") (name "Net-(D1E-A)") (class "Default")
      (node (ref "D1") (pin "5") (pinfunction "A_5") (pintype "passive"))
      (node (ref "IC3") (pin "5") (pinfunction "QF_5") (pintype "tri_state"))
    )
    (net (code "62") (name "Net-(D1E-C)") (class "Default")
      (node (ref "D1") (pin "16") (pinfunction "C_16") (pintype "passive"))
      (node (ref "RN1") (pin "6") (pinfunction "6_6") (pintype "passive"))
    )
    (net (code "63") (name "Net-(D1F-A)") (class "Default")
      (node (ref "D1") (pin "6") (pinfunction "A_6") (pintype "passive"))
      (node (ref "IC3") (pin "4") (pinfunction "QE_4") (pintype "tri_state"))
    )
    (net (code "64") (name "Net-(D1F-C)") (class "Default")
      (node (ref "D1") (pin "15") (pinfunction "C_15") (pintype "passive"))
      (node (ref "RN2") (pin "2") (pinfunction "2_2") (pintype "passive"))
    )
    (net (code "65") (name "Net-(D1G-A)") (class "Default")
      (node (ref "D1") (pin "7") (pinfunction "A_7") (pintype "passive"))
      (node (ref "IC3") (pin "3") (pinfunction "QD_3") (pintype "tri_state"))
    )
    (net (code "66") (name "Net-(D1G-C)") (class "Default")
      (node (ref "D1") (pin "14") (pinfunction "C_14") (pintype "passive"))
      (node (ref "RN2") (pin "3") (pinfunction "3_3") (pintype "passive"))
    )
    (net (code "67") (name "Net-(D1H-A)") (class "Default")
      (node (ref "D1") (pin "8") (pinfunction "A_8") (pintype "passive"))
      (node (ref "IC3") (pin "2") (pinfunction "QC_2") (pintype "tri_state"))
    )
    (net (code "68") (name "Net-(D1H-C)") (class "Default")
      (node (ref "D1") (pin "13") (pinfunction "C_13") (pintype "passive"))
      (node (ref "RN2") (pin "4") (pinfunction "4_4") (pintype "passive"))
    )
    (net (code "69") (name "Net-(D1I-A)") (class "Default")
      (node (ref "D1") (pin "9") (pinfunction "A_9") (pintype "passive"))
      (node (ref "IC3") (pin "1") (pinfunction "QB_1") (pintype "tri_state"))
    )
    (net (code "70") (name "Net-(D1I-C)") (class "Default")
      (node (ref "D1") (pin "12") (pinfunction "C_12") (pintype "passive"))
      (node (ref "RN2") (pin "5") (pinfunction "5_5") (pintype "passive"))
    )
    (net (code "71") (name "Net-(D1J-A)") (class "Default")
      (node (ref "D1") (pin "10") (pinfunction "A_10") (pintype "passive"))
      (node (ref "IC3") (pin "15") (pinfunction "QA_15") (pintype "tri_state"))
    )
    (net (code "72") (name "Net-(D1J-C)") (class "Default")
      (node (ref "D1") (pin "11") (pinfunction "C_11") (pintype "passive"))
      (node (ref "RN2") (pin "6") (pinfunction "6_6") (pintype "passive"))
    )
    (net (code "73") (name "Net-(D2-RS)") (class "Default")
      (node (ref "D2") (pin "8") (pinfunction "RS_8") (pintype "input"))
      (node (ref "R10") (pin "1") (pinfunction "1_1") (pintype "passive"))
    )
    (net (code "74") (name "Net-(IC4-SER)") (class "Default")
      (node (ref "IC4") (pin "10") (pinfunction "SER_10") (pintype "input"))
      (node (ref "R1") (pin "1") (pinfunction "1_1") (pintype "passive"))
    )
    (net (code "75") (name "Net-(LED1-PadA)") (class "Default")
      (node (ref "LED1") (pin "A") (pinfunction "A_A") (pintype "passive"))
      (node (ref "R17") (pin "1") (pinfunction "1_1") (pintype "passive"))
    )
    (net (code "76") (name "Net-(R15-Pad2)") (class "Default")
      (node (ref "R15") (pin "2") (pinfunction "2_2") (pintype "passive"))
      (node (ref "USB") (pin "2") (pinfunction "2_2") (pintype "passive"))
    )
    (net (code "77") (name "Net-(R16-Pad2)") (class "Default")
      (node (ref "R16") (pin "2") (pinfunction "2_2") (pintype "passive"))
      (node (ref "USB") (pin "3") (pinfunction "3_3") (pintype "passive"))
    )
    (net (code "78") (name "unconnected-(CPU1-PA8-Pad41)") (class "Default")
      (node (ref "CPU1") (pin "41") (pinfunction "PA8_41") (pintype "bidirectional"))
    )
    (net (code "79") (name "unconnected-(CPU1-PA10{slash}UART1_RX-Pad43)") (class "Default")
      (node (ref "CPU1") (pin "43") (pinfunction "PA10/UART1_RX_43") (pintype "bidirectional"))
    )
    (net (code "80") (name "unconnected-(CPU1-PA15{slash}JTDI-Pad50)") (class "Default")
      (node (ref "CPU1") (pin "50") (pinfunction "PA15/JTDI_50") (pintype "bidirectional"))
    )
    (net (code "81") (name "unconnected-(CPU1-PB0-Pad26)") (class "Default")
      (node (ref "CPU1") (pin "26") (pinfunction "PB0_26") (pintype "bidirectional"))
    )
    (net (code "82") (name "unconnected-(CPU1-PB1-Pad27)") (class "Default")
      (node (ref "CPU1") (pin "27") (pinfunction "PB1_27") (pintype "bidirectional"))
    )
    (net (code "83") (name "unconnected-(CPU1-PB10-Pad29)") (class "Default")
      (node (ref "CPU1") (pin "29") (pinfunction "PB10_29") (pintype "bidirectional"))
    )
    (net (code "84") (name "unconnected-(CPU1-PB11-Pad30)") (class "Default")
      (node (ref "CPU1") (pin "30") (pinfunction "PB11_30") (pintype "bidirectional"))
    )
    (net (code "85") (name "unconnected-(CPU1-PC0-Pad8)") (class "Default")
      (node (ref "CPU1") (pin "8") (pinfunction "PC0_8") (pintype "bidirectional"))
    )
    (net (code "86") (name "unconnected-(CPU1-PC1-Pad9)") (class "Default")
      (node (ref "CPU1") (pin "9") (pinfunction "PC1_9") (pintype "bidirectional"))
    )
    (net (code "87") (name "unconnected-(CPU1-PC2-Pad10)") (class "Default")
      (node (ref "CPU1") (pin "10") (pinfunction "PC2_10") (pintype "bidirectional"))
    )
    (net (code "88") (name "unconnected-(CPU1-PC3-Pad11)") (class "Default")
      (node (ref "CPU1") (pin "11") (pinfunction "PC3_11") (pintype "bidirectional"))
    )
    (net (code "89") (name "unconnected-(CPU1-PC4-Pad24)") (class "Default")
      (node (ref "CPU1") (pin "24") (pinfunction "PC4_24") (pintype "bidirectional"))
    )
    (net (code "90") (name "unconnected-(CPU1-PC5-Pad25)") (class "Default")
      (node (ref "CPU1") (pin "25") (pinfunction "PC5_25") (pintype "bidirectional"))
    )
    (net (code "91") (name "unconnected-(CPU1-PC9{slash}SDIO_D1-Pad40)") (class "Default")
      (node (ref "CPU1") (pin "40") (pinfunction "PC9/SDIO_D1_40") (pintype "bidirectional"))
    )
    (net (code "92") (name "unconnected-(CPU1-PC12{slash}SDIO_CLK-Pad53)") (class "Default")
      (node (ref "CPU1") (pin "53") (pinfunction "PC12/SDIO_CLK_53") (pintype "bidirectional"))
    )
    (net (code "93") (name "unconnected-(CPU1-PC13-Pad2)") (class "Default")
      (node (ref "CPU1") (pin "2") (pinfunction "PC13_2") (pintype "bidirectional"))
    )
    (net (code "94") (name "unconnected-(CPU1-PC14-Pad3)") (class "Default")
      (node (ref "CPU1") (pin "3") (pinfunction "PC14_3") (pintype "bidirectional"))
    )
    (net (code "95") (name "unconnected-(CPU1-PC15-Pad4)") (class "Default")
      (node (ref "CPU1") (pin "4") (pinfunction "PC15_4") (pintype "bidirectional"))
    )
    (net (code "96") (name "unconnected-(CPU1-PD2{slash}SDIO_CMD-Pad54)") (class "Default")
      (node (ref "CPU1") (pin "54") (pinfunction "PD2/SDIO_CMD_54") (pintype "bidirectional"))
    )
    (net (code "97") (name "unconnected-(D1A-A-Pad1)") (class "Default")
      (node (ref "D1") (pin "1") (pinfunction "A_1") (pintype "passive"))
    )
    (net (code "98") (name "unconnected-(D1B-A-Pad2)") (class "Default")
      (node (ref "D1") (pin "2") (pinfunction "A_2") (pintype "passive"))
    )
    (net (code "99") (name "unconnected-(D2-VREF-Pad5)") (class "Default")
      (node (ref "D2") (pin "5") (pinfunction "VREF_5") (pintype "output"))
    )
    (net (code "100") (name "unconnected-(IC3-QH*-Pad9)") (class "Default")
      (node (ref "IC3") (pin "9") (pinfunction "QH*_9") (pintype "tri_state"))
    )
    (net (code "101") (name "unconnected-(IC4-~{QH}-Pad7)") (class "Default")
      (node (ref "IC4") (pin "7") (pinfunction "~{QH}_7") (pintype "input"))
    )
  )
)
